# 2DD-17-mk-1_3.net
KiCad netlist of a schematic drawn in EAGLE
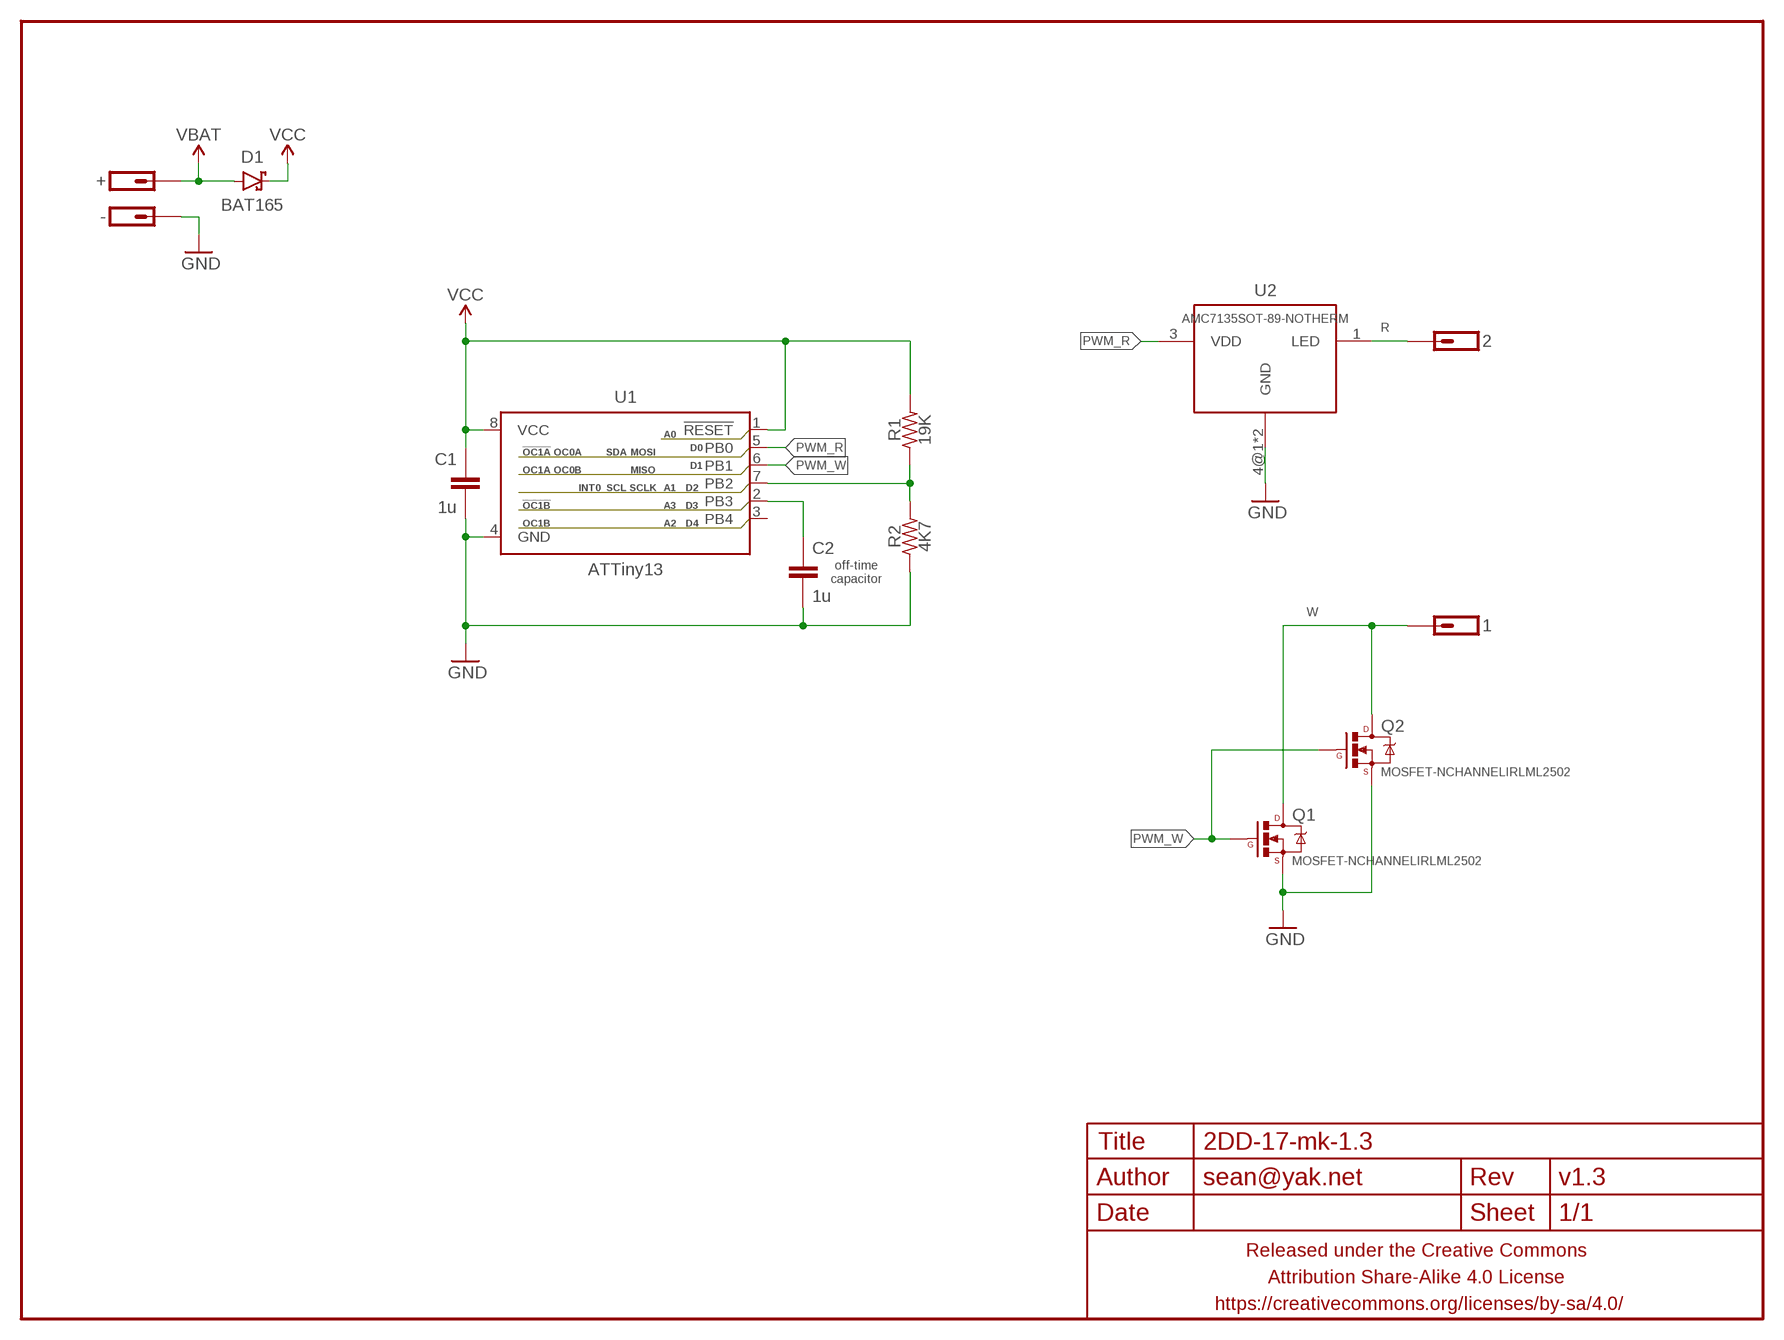
[diagram p0: schematic, sheet 1]

(export (version "E")
  (design (tool "Eeschema 10.0.6"))
  (components
    (comp (ref "+")
      (value "M01PTH-1MM-CIR-NS")
      (footprint "eagle-import:1X01-1MM-CIR-NS")
      (libsource (lib "eagle-import") (part "M01PTH-1MM-CIR-NS"))
    )
    (comp (ref "-")
      (value "M01NOT-A-VIA-NOPE")
      (footprint "eagle-import:1X01_NOSILK_NOSTOP")
      (libsource (lib "eagle-import") (part "M01NOT-A-VIA-NOPE"))
    )
    (comp (ref "1")
      (value "M01SMD-1.25MM-DIA")
      (footprint "eagle-import:1X01-SMD-1.25MM-DIA-NS")
      (libsource (lib "eagle-import") (part "M01SMD-1.25MM-DIA"))
    )
    (comp (ref "2")
      (value "M01SMD-1.25MM-DIA")
      (footprint "eagle-import:1X01-SMD-1.25MM-DIA-NS")
      (libsource (lib "eagle-import") (part "M01SMD-1.25MM-DIA"))
    )
    (comp (ref "C1")
      (value "1u")
      (footprint "eagle-import:C0603-TIGHTER")
      (libsource (lib "eagle-import") (part "CAPACITOR-CERAMICC0603-TIGHTER"))
    )
    (comp (ref "C2")
      (value "1u")
      (footprint "eagle-import:C0603-TIGHTER")
      (libsource (lib "eagle-import") (part "CAPACITOR-CERAMICC0603-TIGHTER"))
    )
    (comp (ref "D1")
      (value "BAT165")
      (footprint "eagle-import:SOD323-SCHOTTKY")
      (libsource (lib "eagle-import") (part "DIODE-SCHOTTKYSOD323"))
    )
    (comp (ref "FRAME1")
      (value "FRAME-LETTERNO_PACKAGE")
      (footprint "eagle-import:DUMMY")
      (fields (field (name "DESIGNER") "sean@yak.net") (field (name "VERSION") "v1.3"))
      (libsource (lib "eagle-import") (part "FRAME-LETTERNO_PACKAGE"))
    )
    (comp (ref "Q1")
      (value "MOSFET-NCHANNELIRLML2502")
      (footprint "eagle-import:SOT23")
      (libsource (lib "eagle-import") (part "MOSFET-NCHANNELIRLML2502"))
    )
    (comp (ref "Q2")
      (value "MOSFET-NCHANNELIRLML2502")
      (footprint "eagle-import:SOT23")
      (libsource (lib "eagle-import") (part "MOSFET-NCHANNELIRLML2502"))
    )
    (comp (ref "R1")
      (value "19K")
      (footprint "eagle-import:R0603-TIGHTER")
      (libsource (lib "eagle-import") (part "RESISTORR0603-TIGHTER"))
    )
    (comp (ref "R2")
      (value "4K7")
      (footprint "eagle-import:R0603-TIGHTER")
      (libsource (lib "eagle-import") (part "RESISTORR0603-TIGHTER"))
    )
    (comp (ref "U1")
      (value "ATTiny13")
      (footprint "eagle-import:SO08-NARROWER")
      (libsource (lib "eagle-import") (part "ATTINY13SOIC-NARROWPADS"))
    )
    (comp (ref "U2")
      (value "AMC7135SOT-89-NOTHERM")
      (footprint "eagle-import:SOT89-NOTHERM")
      (libsource (lib "eagle-import") (part "AMC7135SOT-89-NOTHERM"))
    )
  )
  (nets
    (net (code "1") (name "/R") (class "Default")
      (node (ref "2") (pin "P$1") (pinfunction "1_P$1") (pintype "passive"))
      (node (ref "U2") (pin "1") (pinfunction "LED_1") (pintype "bidirectional"))
    )
    (net (code "2") (name "/W") (class "Default")
      (node (ref "1") (pin "P$1") (pinfunction "1_P$1") (pintype "passive"))
      (node (ref "Q1") (pin "3") (pinfunction "D_3") (pintype "passive"))
      (node (ref "Q2") (pin "3") (pinfunction "D_3") (pintype "passive"))
    )
    (net (code "3") (name "GND") (class "Default")
      (node (ref "-") (pin "P$1") (pinfunction "1_P$1") (pintype "passive"))
      (node (ref "C1") (pin "2") (pinfunction "2_2") (pintype "passive"))
      (node (ref "C2") (pin "2") (pinfunction "2_2") (pintype "passive"))
      (node (ref "Q1") (pin "2") (pinfunction "S_2") (pintype "passive"))
      (node (ref "Q2") (pin "2") (pinfunction "S_2") (pintype "passive"))
      (node (ref "R2") (pin "1") (pinfunction "1_1") (pintype "passive"))
      (node (ref "U1") (pin "4") (pinfunction "GND_4") (pintype "bidirectional"))
      (node (ref "U2") (pin "4@1") (pinfunction "GND_4@1") (pintype "bidirectional"))
      (node (ref "U2") (pin "4@2") (pinfunction "GND_4@2") (pintype "bidirectional"))
    )
    (net (code "4") (name "Net-(U1-PB2)") (class "Default")
      (node (ref "R1") (pin "1") (pinfunction "1_1") (pintype "passive"))
      (node (ref "R2") (pin "2") (pinfunction "2_2") (pintype "passive"))
      (node (ref "U1") (pin "7") (pinfunction "PB2_7") (pintype "bidirectional"))
    )
    (net (code "5") (name "Net-(U1-PB3)") (class "Default")
      (node (ref "C2") (pin "1") (pinfunction "1_1") (pintype "passive"))
      (node (ref "U1") (pin "2") (pinfunction "PB3_2") (pintype "bidirectional"))
    )
    (net (code "6") (name "PWM_R") (class "Default")
      (node (ref "U1") (pin "5") (pinfunction "PB0_5") (pintype "bidirectional"))
      (node (ref "U2") (pin "3") (pinfunction "VDD_3") (pintype "bidirectional"))
    )
    (net (code "7") (name "PWM_W") (class "Default")
      (node (ref "Q1") (pin "1") (pinfunction "G_1") (pintype "passive"))
      (node (ref "Q2") (pin "1") (pinfunction "G_1") (pintype "passive"))
      (node (ref "U1") (pin "6") (pinfunction "PB1_6") (pintype "bidirectional"))
    )
    (net (code "8") (name "VBAT") (class "Default")
      (node (ref "+") (pin "1") (pinfunction "1_1") (pintype "passive"))
      (node (ref "D1") (pin "A") (pinfunction "A_A") (pintype "passive"))
    )
    (net (code "9") (name "VCC") (class "Default")
      (node (ref "C1") (pin "1") (pinfunction "1_1") (pintype "passive"))
      (node (ref "D1") (pin "C") (pinfunction "C_C") (pintype "passive"))
      (node (ref "R1") (pin "2") (pinfunction "2_2") (pintype "passive"))
      (node (ref "U1") (pin "1") (pinfunction "~{RESET}_1") (pintype "bidirectional"))
      (node (ref "U1") (pin "8") (pinfunction "VCC_8") (pintype "bidirectional"))
    )
    (net (code "10") (name "unconnected-(U1-PB4-Pad3)") (class "Default")
      (node (ref "U1") (pin "3") (pinfunction "PB4_3") (pintype "bidirectional"))
    )
  )
)
